# USB.net
KiCad netlist of a schematic drawn in Altium Designer
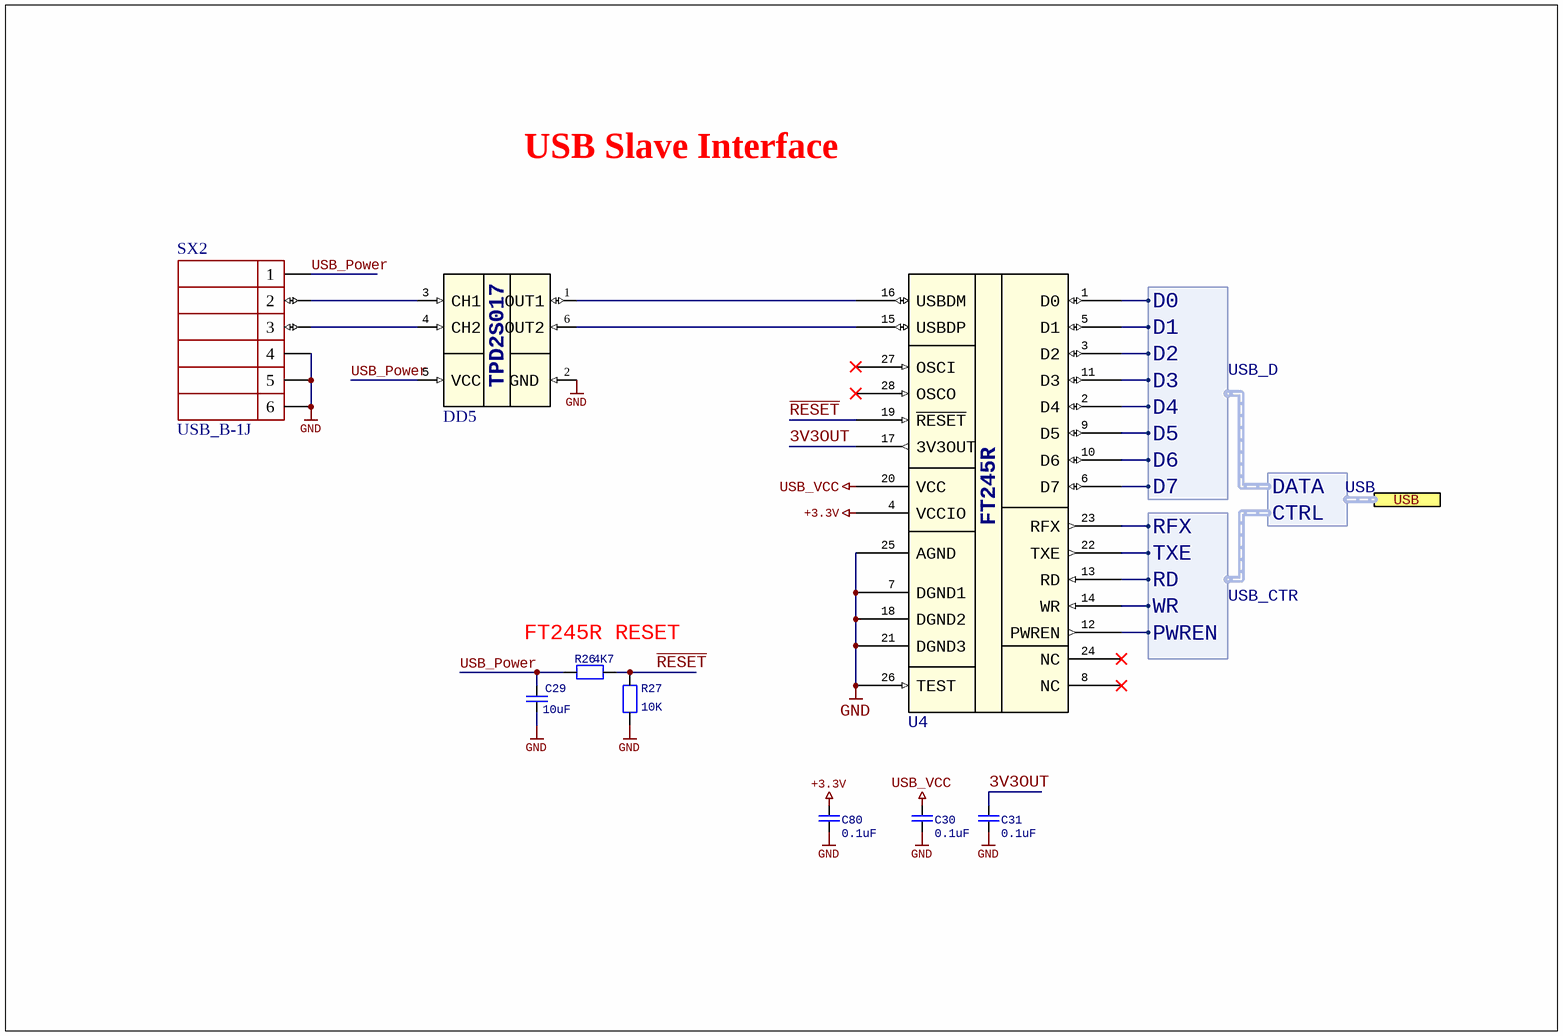
[diagram p0: USB.SchDoc]

(export (version "E")
  (design (tool "Eeschema 10.0.6"))
  (components
    (comp (ref "C29")
      (value "10uF")
      (footprint "Passive:C_0603")
      (description "Non-polarised capacitor")
      (libsource (lib "Passive") (part "C"))
    )
    (comp (ref "C30")
      (value "0.1uF")
      (footprint "Passive:C_0603")
      (description "Non-polarised capacitor")
      (libsource (lib "Passive") (part "C"))
    )
    (comp (ref "C31")
      (value "0.1uF")
      (footprint "Passive:C_0603")
      (description "Non-polarised capacitor")
      (libsource (lib "Passive") (part "C"))
    )
    (comp (ref "C80")
      (value "0.1uF")
      (footprint "Passive:C_0603")
      (description "Non-polarised capacitor")
      (libsource (lib "Passive") (part "C"))
    )
    (comp (ref "DD5")
      (value "TPD2S017")
      (footprint "SOT:SOT-23-6")
      (libsource (lib "Device") (part "TPD2S017"))
    )
    (comp (ref "R26") (value "4K7") (footprint "Passive:R_0603") (libsource (lib "Passive") (part "R")))
    (comp (ref "R27") (value "10K") (footprint "Passive:R_0603") (libsource (lib "") (part "R_1")))
    (comp (ref "SX2")
      (value "USB_B-1J")
      (footprint "Connectors_USB:USB_B_(DS1099)")
      (libsource (lib "Connector") (part "USBA-1J"))
    )
    (comp (ref "U4") (value "FT245R") (footprint "SOP:SSOP- 28") (libsource (lib "Device") (part "FT245R")))
  )
  (nets
    (net (code "4") (name "+3.3V") (class "Default")
      (node (ref "C80") (pin "1") (pinfunction "1_1") (pintype "passive"))
      (node (ref "U4") (pin "4") (pinfunction "VCCIO_4") (pintype "power_in"))
    )
    (net (code "5") (name "/3V3OUT") (class "Default")
      (node (ref "C31") (pin "1") (pinfunction "1_1") (pintype "passive"))
      (node (ref "U4") (pin "17") (pinfunction "3V3OUT_17") (pintype "output"))
    )
    (net (code "6") (name "/D0") (class "Default")
      (node (ref "U4") (pin "1") (pinfunction "D0_1") (pintype "bidirectional"))
    )
    (net (code "7") (name "/D1") (class "Default")
      (node (ref "U4") (pin "5") (pinfunction "D1_5") (pintype "bidirectional"))
    )
    (net (code "8") (name "/D2") (class "Default")
      (node (ref "U4") (pin "3") (pinfunction "D2_3") (pintype "bidirectional"))
    )
    (net (code "9") (name "/D3") (class "Default")
      (node (ref "U4") (pin "11") (pinfunction "D3_11") (pintype "bidirectional"))
    )
    (net (code "10") (name "/D4") (class "Default")
      (node (ref "U4") (pin "2") (pinfunction "D4_2") (pintype "bidirectional"))
    )
    (net (code "11") (name "/D5") (class "Default")
      (node (ref "U4") (pin "9") (pinfunction "D5_9") (pintype "bidirectional"))
    )
    (net (code "12") (name "/D6") (class "Default")
      (node (ref "U4") (pin "10") (pinfunction "D6_10") (pintype "bidirectional"))
    )
    (net (code "13") (name "/D7") (class "Default")
      (node (ref "U4") (pin "6") (pinfunction "D7_6") (pintype "bidirectional"))
    )
    (net (code "14") (name "/PWREN") (class "Default")
      (node (ref "U4") (pin "12") (pinfunction "PWREN_12") (pintype "output"))
    )
    (net (code "15") (name "/RD") (class "Default")
      (node (ref "U4") (pin "13") (pinfunction "RD_13") (pintype "input"))
    )
    (net (code "16") (name "/RESET") (class "Default")
      (node (ref "R26") (pin "2") (pinfunction "2_2") (pintype "passive"))
      (node (ref "R27") (pin "1") (pinfunction "1_1") (pintype "passive"))
      (node (ref "U4") (pin "19") (pinfunction "RESET_19") (pintype "input"))
    )
    (net (code "17") (name "/RFX") (class "Default")
      (node (ref "U4") (pin "23") (pinfunction "RFX_23") (pintype "output"))
    )
    (net (code "18") (name "/TXE") (class "Default")
      (node (ref "U4") (pin "22") (pinfunction "TXE_22") (pintype "output"))
    )
    (net (code "19") (name "/USB_Power") (class "Default")
      (node (ref "C29") (pin "2") (pinfunction "2_2") (pintype "passive"))
      (node (ref "DD5") (pin "5") (pinfunction "VCC_5") (pintype "input"))
      (node (ref "R26") (pin "1") (pinfunction "1_1") (pintype "passive"))
      (node (ref "SX2") (pin "1") (pinfunction "1_1") (pintype "passive"))
    )
    (net (code "21") (name "/WR") (class "Default")
      (node (ref "U4") (pin "14") (pinfunction "WR_14") (pintype "input"))
    )
    (net (code "24") (name "GND") (class "Default")
      (node (ref "C29") (pin "1") (pinfunction "1_1") (pintype "passive"))
      (node (ref "C30") (pin "2") (pinfunction "2_2") (pintype "passive"))
      (node (ref "C31") (pin "2") (pinfunction "2_2") (pintype "passive"))
      (node (ref "C80") (pin "2") (pinfunction "2_2") (pintype "passive"))
      (node (ref "DD5") (pin "2") (pinfunction "GND_2") (pintype "input"))
      (node (ref "R27") (pin "2") (pinfunction "2_2") (pintype "passive"))
      (node (ref "SX2") (pin "4") (pinfunction "4_4") (pintype "passive"))
      (node (ref "SX2") (pin "5") (pinfunction "5_5") (pintype "passive"))
      (node (ref "SX2") (pin "6") (pinfunction "6_6") (pintype "passive"))
      (node (ref "U4") (pin "18") (pinfunction "DGND2_18") (pintype "power_in"))
      (node (ref "U4") (pin "21") (pinfunction "DGND3_21") (pintype "power_in"))
      (node (ref "U4") (pin "25") (pinfunction "AGND_25") (pintype "power_in"))
      (node (ref "U4") (pin "26") (pinfunction "TEST_26") (pintype "input"))
      (node (ref "U4") (pin "7") (pinfunction "DGND1_7") (pintype "power_in"))
    )
    (net (code "25") (name "Net-(DD5-CH1)") (class "Default")
      (node (ref "DD5") (pin "3") (pinfunction "CH1_3") (pintype "input"))
      (node (ref "SX2") (pin "2") (pinfunction "2_2") (pintype "bidirectional"))
    )
    (net (code "26") (name "Net-(DD5-CH2)") (class "Default")
      (node (ref "DD5") (pin "4") (pinfunction "CH2_4") (pintype "input"))
      (node (ref "SX2") (pin "3") (pinfunction "3_3") (pintype "bidirectional"))
    )
    (net (code "27") (name "Net-(DD5-OUT1)") (class "Default")
      (node (ref "DD5") (pin "1") (pinfunction "OUT1_1") (pintype "bidirectional"))
      (node (ref "U4") (pin "16") (pinfunction "USBDM_16") (pintype "bidirectional"))
    )
    (net (code "28") (name "Net-(DD5-OUT2)") (class "Default")
      (node (ref "DD5") (pin "6") (pinfunction "OUT2_6") (pintype "input"))
      (node (ref "U4") (pin "15") (pinfunction "USBDP_15") (pintype "bidirectional"))
    )
    (net (code "29") (name "USB_VCC") (class "Default")
      (node (ref "C30") (pin "1") (pinfunction "1_1") (pintype "passive"))
      (node (ref "U4") (pin "20") (pinfunction "VCC_20") (pintype "power_in"))
    )
    (net (code "30") (name "unconnected-(U4-NC-Pad8)") (class "Default")
      (node (ref "U4") (pin "8") (pinfunction "NC_8") (pintype "passive+no_connect"))
    )
    (net (code "31") (name "unconnected-(U4-NC-Pad24)") (class "Default")
      (node (ref "U4") (pin "24") (pinfunction "NC_24") (pintype "passive+no_connect"))
    )
    (net (code "32") (name "unconnected-(U4-OSCI-Pad27)") (class "Default")
      (node (ref "U4") (pin "27") (pinfunction "OSCI_27") (pintype "input+no_connect"))
    )
    (net (code "33") (name "unconnected-(U4-OSCO-Pad28)") (class "Default")
      (node (ref "U4") (pin "28") (pinfunction "OSCO_28") (pintype "input+no_connect"))
    )
  )
)
